# MotorDrive1.net
KiCad netlist of a schematic drawn in Altium Designer
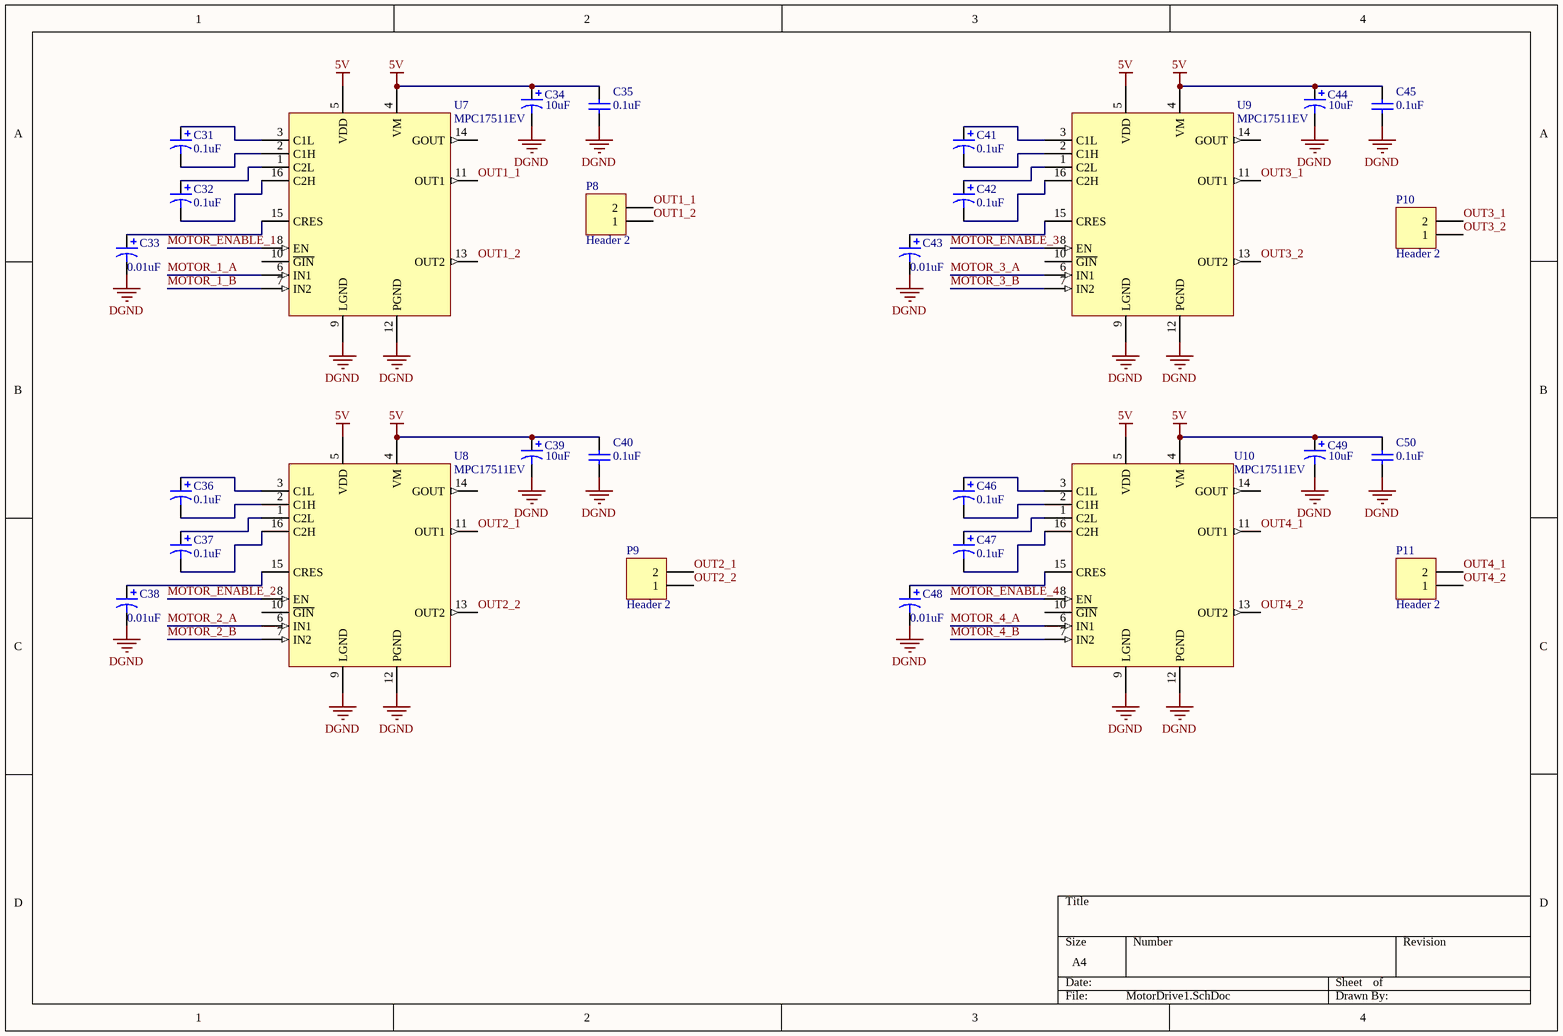
[diagram p0: MotorDrive1.SchDoc]

(export (version "E")
  (design (tool "Eeschema 10.0.6"))
  (components
    (comp (ref "C31")
      (value "0.1uF")
      (footprint "0402")
      (description "Polarized Capacitor (Radial)")
      (fields (field (name "PUBLISHER") "Altium Limited"))
      (libsource (lib "Miscellaneous Devices") (part "Cap Pol1"))
    )
    (comp (ref "C32")
      (value "0.1uF")
      (footprint "0402")
      (description "Polarized Capacitor (Radial)")
      (fields (field (name "PUBLISHER") "Altium Limited"))
      (libsource (lib "Miscellaneous Devices") (part "Cap Pol1"))
    )
    (comp (ref "C33")
      (value "0.01uF")
      (footprint "1608[0603]")
      (description "Polarized Capacitor (Radial)")
      (fields (field (name "PUBLISHER") "Altium Limited"))
      (libsource (lib "Miscellaneous Devices") (part "Cap Pol1"))
    )
    (comp (ref "C34")
      (value "10uF")
      (footprint "1608[0603]")
      (description "Polarized Capacitor (Radial)")
      (fields (field (name "PUBLISHER") "Altium Limited"))
      (libsource (lib "Miscellaneous Devices") (part "Cap Pol1"))
    )
    (comp (ref "C35")
      (value "0.1uF")
      (footprint "1608[0603]")
      (description "Capacitor")
      (fields (field (name "PUBLISHER") "Altium Limited"))
      (libsource (lib "Miscellaneous Devices") (part "Cap"))
    )
    (comp (ref "C36")
      (value "0.1uF")
      (footprint "0402")
      (description "Polarized Capacitor (Radial)")
      (fields (field (name "PUBLISHER") "Altium Limited"))
      (libsource (lib "Miscellaneous Devices") (part "Cap Pol1"))
    )
    (comp (ref "C37")
      (value "0.1uF")
      (footprint "0402")
      (description "Polarized Capacitor (Radial)")
      (fields (field (name "PUBLISHER") "Altium Limited"))
      (libsource (lib "Miscellaneous Devices") (part "Cap Pol1"))
    )
    (comp (ref "C38")
      (value "0.01uF")
      (footprint "1608[0603]")
      (description "Polarized Capacitor (Radial)")
      (fields (field (name "PUBLISHER") "Altium Limited"))
      (libsource (lib "Miscellaneous Devices") (part "Cap Pol1"))
    )
    (comp (ref "C39")
      (value "10uF")
      (footprint "1608[0603]")
      (description "Polarized Capacitor (Radial)")
      (fields (field (name "PUBLISHER") "Altium Limited"))
      (libsource (lib "Miscellaneous Devices") (part "Cap Pol1"))
    )
    (comp (ref "C40")
      (value "0.1uF")
      (footprint "1608[0603]")
      (description "Capacitor")
      (fields (field (name "PUBLISHER") "Altium Limited"))
      (libsource (lib "Miscellaneous Devices") (part "Cap"))
    )
    (comp (ref "C41")
      (value "0.1uF")
      (footprint "0402")
      (description "Polarized Capacitor (Radial)")
      (fields (field (name "PUBLISHER") "Altium Limited"))
      (libsource (lib "Miscellaneous Devices") (part "Cap Pol1"))
    )
    (comp (ref "C42")
      (value "0.1uF")
      (footprint "0402")
      (description "Polarized Capacitor (Radial)")
      (fields (field (name "PUBLISHER") "Altium Limited"))
      (libsource (lib "Miscellaneous Devices") (part "Cap Pol1"))
    )
    (comp (ref "C43")
      (value "0.01uF")
      (footprint "1608[0603]")
      (description "Polarized Capacitor (Radial)")
      (fields (field (name "PUBLISHER") "Altium Limited"))
      (libsource (lib "Miscellaneous Devices") (part "Cap Pol1"))
    )
    (comp (ref "C44")
      (value "10uF")
      (footprint "1608[0603]")
      (description "Polarized Capacitor (Radial)")
      (fields (field (name "PUBLISHER") "Altium Limited"))
      (libsource (lib "Miscellaneous Devices") (part "Cap Pol1"))
    )
    (comp (ref "C45")
      (value "0.1uF")
      (footprint "1608[0603]")
      (description "Capacitor")
      (fields (field (name "PUBLISHER") "Altium Limited"))
      (libsource (lib "Miscellaneous Devices") (part "Cap"))
    )
    (comp (ref "C46")
      (value "0.1uF")
      (footprint "0402")
      (description "Polarized Capacitor (Radial)")
      (fields (field (name "PUBLISHER") "Altium Limited"))
      (libsource (lib "Miscellaneous Devices") (part "Cap Pol1"))
    )
    (comp (ref "C47")
      (value "0.1uF")
      (footprint "0402")
      (description "Polarized Capacitor (Radial)")
      (fields (field (name "PUBLISHER") "Altium Limited"))
      (libsource (lib "Miscellaneous Devices") (part "Cap Pol1"))
    )
    (comp (ref "C48")
      (value "0.01uF")
      (footprint "1608[0603]")
      (description "Polarized Capacitor (Radial)")
      (fields (field (name "PUBLISHER") "Altium Limited"))
      (libsource (lib "Miscellaneous Devices") (part "Cap Pol1"))
    )
    (comp (ref "C49")
      (value "10uF")
      (footprint "1608[0603]")
      (description "Polarized Capacitor (Radial)")
      (fields (field (name "PUBLISHER") "Altium Limited"))
      (libsource (lib "Miscellaneous Devices") (part "Cap Pol1"))
    )
    (comp (ref "C50")
      (value "0.1uF")
      (footprint "1608[0603]")
      (description "Capacitor")
      (fields (field (name "PUBLISHER") "Altium Limited"))
      (libsource (lib "Miscellaneous Devices") (part "Cap"))
    )
    (comp (ref "P8")
      (value "Header 2")
      (footprint "HDR1X2")
      (description "Header, 2-Pin")
      (fields (field (name "PUBLISHER") "Altium Limited"))
      (libsource (lib "Miscellaneous Connectors") (part "Header 2"))
    )
    (comp (ref "P9")
      (value "Header 2")
      (footprint "HDR1X2")
      (description "Header, 2-Pin")
      (fields (field (name "PUBLISHER") "Altium Limited"))
      (libsource (lib "Miscellaneous Connectors") (part "Header 2"))
    )
    (comp (ref "P10")
      (value "Header 2")
      (footprint "HDR1X2")
      (description "Header, 2-Pin")
      (fields (field (name "PUBLISHER") "Altium Limited"))
      (libsource (lib "Miscellaneous Connectors") (part "Header 2"))
    )
    (comp (ref "P11")
      (value "Header 2")
      (footprint "HDR1X2")
      (description "Header, 2-Pin")
      (fields (field (name "PUBLISHER") "Altium Limited"))
      (libsource (lib "Miscellaneous Connectors") (part "Header 2"))
    )
    (comp (ref "U7")
      (value "MPC17511EV")
      (footprint "MPC_motor_drive")
      (description "IC MOTOR DRIVER PAR 16VMFP")
      (libsource (lib "MPC_motor_driver") (part "MPC17511EV"))
    )
    (comp (ref "U8")
      (value "MPC17511EV")
      (footprint "MPC_motor_drive")
      (description "IC MOTOR DRIVER PAR 16VMFP")
      (libsource (lib "MPC_motor_driver") (part "MPC17511EV"))
    )
    (comp (ref "U9")
      (value "MPC17511EV")
      (footprint "MPC_motor_drive")
      (description "IC MOTOR DRIVER PAR 16VMFP")
      (libsource (lib "MPC_motor_driver") (part "MPC17511EV"))
    )
    (comp (ref "U10")
      (value "MPC17511EV")
      (footprint "MPC_motor_drive")
      (description "IC MOTOR DRIVER PAR 16VMFP")
      (libsource (lib "MPC_motor_driver") (part "MPC17511EV"))
    )
  )
  (nets
    (net (code "1") (name "/MOTOR_1_A") (class "Default")
      (node (ref "U7") (pin "6") (pinfunction "IN1_6") (pintype "input"))
    )
    (net (code "2") (name "/MOTOR_1_B") (class "Default")
      (node (ref "U7") (pin "7") (pinfunction "IN2_7") (pintype "input"))
    )
    (net (code "3") (name "/MOTOR_2_A") (class "Default")
      (node (ref "U8") (pin "6") (pinfunction "IN1_6") (pintype "input"))
    )
    (net (code "4") (name "/MOTOR_2_B") (class "Default")
      (node (ref "U8") (pin "7") (pinfunction "IN2_7") (pintype "input"))
    )
    (net (code "5") (name "/MOTOR_3_A") (class "Default")
      (node (ref "U9") (pin "6") (pinfunction "IN1_6") (pintype "input"))
    )
    (net (code "6") (name "/MOTOR_3_B") (class "Default")
      (node (ref "U9") (pin "7") (pinfunction "IN2_7") (pintype "input"))
    )
    (net (code "7") (name "/MOTOR_4_A") (class "Default")
      (node (ref "U10") (pin "6") (pinfunction "IN1_6") (pintype "input"))
    )
    (net (code "8") (name "/MOTOR_4_B") (class "Default")
      (node (ref "U10") (pin "7") (pinfunction "IN2_7") (pintype "input"))
    )
    (net (code "9") (name "/MOTOR_ENABLE_1") (class "Default")
      (node (ref "U7") (pin "8") (pinfunction "EN_8") (pintype "input"))
    )
    (net (code "10") (name "/MOTOR_ENABLE_2") (class "Default")
      (node (ref "U8") (pin "8") (pinfunction "EN_8") (pintype "input"))
    )
    (net (code "11") (name "/MOTOR_ENABLE_3") (class "Default")
      (node (ref "U9") (pin "8") (pinfunction "EN_8") (pintype "input"))
    )
    (net (code "12") (name "/MOTOR_ENABLE_4") (class "Default")
      (node (ref "U10") (pin "8") (pinfunction "EN_8") (pintype "input"))
    )
    (net (code "13") (name "/OUT1_1") (class "Default")
      (node (ref "P8") (pin "2") (pinfunction "2_2") (pintype "passive"))
      (node (ref "U7") (pin "11") (pinfunction "OUT1_11") (pintype "output"))
    )
    (net (code "14") (name "/OUT1_2") (class "Default")
      (node (ref "P8") (pin "1") (pinfunction "1_1") (pintype "passive"))
      (node (ref "U7") (pin "13") (pinfunction "OUT2_13") (pintype "output"))
    )
    (net (code "15") (name "/OUT2_1") (class "Default")
      (node (ref "P9") (pin "2") (pinfunction "2_2") (pintype "passive"))
      (node (ref "U8") (pin "11") (pinfunction "OUT1_11") (pintype "output"))
    )
    (net (code "16") (name "/OUT2_2") (class "Default")
      (node (ref "P9") (pin "1") (pinfunction "1_1") (pintype "passive"))
      (node (ref "U8") (pin "13") (pinfunction "OUT2_13") (pintype "output"))
    )
    (net (code "17") (name "/OUT3_1") (class "Default")
      (node (ref "P10") (pin "2") (pinfunction "2_2") (pintype "passive"))
      (node (ref "U9") (pin "11") (pinfunction "OUT1_11") (pintype "output"))
    )
    (net (code "18") (name "/OUT3_2") (class "Default")
      (node (ref "P10") (pin "1") (pinfunction "1_1") (pintype "passive"))
      (node (ref "U9") (pin "13") (pinfunction "OUT2_13") (pintype "output"))
    )
    (net (code "19") (name "/OUT4_1") (class "Default")
      (node (ref "P11") (pin "2") (pinfunction "2_2") (pintype "passive"))
      (node (ref "U10") (pin "11") (pinfunction "OUT1_11") (pintype "output"))
    )
    (net (code "20") (name "/OUT4_2") (class "Default")
      (node (ref "P11") (pin "1") (pinfunction "1_1") (pintype "passive"))
      (node (ref "U10") (pin "13") (pinfunction "OUT2_13") (pintype "output"))
    )
    (net (code "21") (name "5V") (class "Default")
      (node (ref "C34") (pin "1") (pinfunction "1_1") (pintype "passive"))
      (node (ref "C35") (pin "2") (pinfunction "2_2") (pintype "passive"))
      (node (ref "C39") (pin "1") (pinfunction "1_1") (pintype "passive"))
      (node (ref "C40") (pin "2") (pinfunction "2_2") (pintype "passive"))
      (node (ref "C44") (pin "1") (pinfunction "1_1") (pintype "passive"))
      (node (ref "C45") (pin "2") (pinfunction "2_2") (pintype "passive"))
      (node (ref "C49") (pin "1") (pinfunction "1_1") (pintype "passive"))
      (node (ref "C50") (pin "2") (pinfunction "2_2") (pintype "passive"))
      (node (ref "U10") (pin "4") (pinfunction "VM_4") (pintype "power_in"))
      (node (ref "U10") (pin "5") (pinfunction "VDD_5") (pintype "power_in"))
      (node (ref "U7") (pin "4") (pinfunction "VM_4") (pintype "power_in"))
      (node (ref "U7") (pin "5") (pinfunction "VDD_5") (pintype "power_in"))
      (node (ref "U8") (pin "4") (pinfunction "VM_4") (pintype "power_in"))
      (node (ref "U8") (pin "5") (pinfunction "VDD_5") (pintype "power_in"))
      (node (ref "U9") (pin "4") (pinfunction "VM_4") (pintype "power_in"))
      (node (ref "U9") (pin "5") (pinfunction "VDD_5") (pintype "power_in"))
    )
    (net (code "22") (name "DGND") (class "Default")
      (node (ref "C33") (pin "2") (pinfunction "2_2") (pintype "passive"))
      (node (ref "C34") (pin "2") (pinfunction "2_2") (pintype "passive"))
      (node (ref "C35") (pin "1") (pinfunction "1_1") (pintype "passive"))
      (node (ref "C38") (pin "2") (pinfunction "2_2") (pintype "passive"))
      (node (ref "C39") (pin "2") (pinfunction "2_2") (pintype "passive"))
      (node (ref "C40") (pin "1") (pinfunction "1_1") (pintype "passive"))
      (node (ref "C43") (pin "2") (pinfunction "2_2") (pintype "passive"))
      (node (ref "C44") (pin "2") (pinfunction "2_2") (pintype "passive"))
      (node (ref "C45") (pin "1") (pinfunction "1_1") (pintype "passive"))
      (node (ref "C48") (pin "2") (pinfunction "2_2") (pintype "passive"))
      (node (ref "C49") (pin "2") (pinfunction "2_2") (pintype "passive"))
      (node (ref "C50") (pin "1") (pinfunction "1_1") (pintype "passive"))
      (node (ref "U10") (pin "12") (pinfunction "PGND_12") (pintype "passive"))
      (node (ref "U10") (pin "9") (pinfunction "LGND_9") (pintype "passive"))
      (node (ref "U7") (pin "12") (pinfunction "PGND_12") (pintype "passive"))
      (node (ref "U7") (pin "9") (pinfunction "LGND_9") (pintype "passive"))
      (node (ref "U8") (pin "12") (pinfunction "PGND_12") (pintype "passive"))
      (node (ref "U8") (pin "9") (pinfunction "LGND_9") (pintype "passive"))
      (node (ref "U9") (pin "12") (pinfunction "PGND_12") (pintype "passive"))
      (node (ref "U9") (pin "9") (pinfunction "LGND_9") (pintype "passive"))
    )
    (net (code "23") (name "Net-(U7-C1H)") (class "Default")
      (node (ref "C31") (pin "2") (pinfunction "2_2") (pintype "passive"))
      (node (ref "U7") (pin "2") (pinfunction "C1H_2") (pintype "passive"))
    )
    (net (code "24") (name "Net-(U7-C1L)") (class "Default")
      (node (ref "C31") (pin "1") (pinfunction "1_1") (pintype "passive"))
      (node (ref "U7") (pin "3") (pinfunction "C1L_3") (pintype "passive"))
    )
    (net (code "25") (name "Net-(U7-C2H)") (class "Default")
      (node (ref "C32") (pin "2") (pinfunction "2_2") (pintype "passive"))
      (node (ref "U7") (pin "16") (pinfunction "C2H_16") (pintype "passive"))
    )
    (net (code "26") (name "Net-(U7-C2L)") (class "Default")
      (node (ref "C32") (pin "1") (pinfunction "1_1") (pintype "passive"))
      (node (ref "U7") (pin "1") (pinfunction "C2L_1") (pintype "passive"))
    )
    (net (code "27") (name "Net-(U7-CRES)") (class "Default")
      (node (ref "C33") (pin "1") (pinfunction "1_1") (pintype "passive"))
      (node (ref "U7") (pin "15") (pinfunction "CRES_15") (pintype "passive"))
    )
    (net (code "28") (name "Net-(U8-C1H)") (class "Default")
      (node (ref "C36") (pin "2") (pinfunction "2_2") (pintype "passive"))
      (node (ref "U8") (pin "2") (pinfunction "C1H_2") (pintype "passive"))
    )
    (net (code "29") (name "Net-(U8-C1L)") (class "Default")
      (node (ref "C36") (pin "1") (pinfunction "1_1") (pintype "passive"))
      (node (ref "U8") (pin "3") (pinfunction "C1L_3") (pintype "passive"))
    )
    (net (code "30") (name "Net-(U8-C2H)") (class "Default")
      (node (ref "C37") (pin "2") (pinfunction "2_2") (pintype "passive"))
      (node (ref "U8") (pin "16") (pinfunction "C2H_16") (pintype "passive"))
    )
    (net (code "31") (name "Net-(U8-C2L)") (class "Default")
      (node (ref "C37") (pin "1") (pinfunction "1_1") (pintype "passive"))
      (node (ref "U8") (pin "1") (pinfunction "C2L_1") (pintype "passive"))
    )
    (net (code "32") (name "Net-(U8-CRES)") (class "Default")
      (node (ref "C38") (pin "1") (pinfunction "1_1") (pintype "passive"))
      (node (ref "U8") (pin "15") (pinfunction "CRES_15") (pintype "passive"))
    )
    (net (code "33") (name "Net-(U9-C1H)") (class "Default")
      (node (ref "C41") (pin "2") (pinfunction "2_2") (pintype "passive"))
      (node (ref "U9") (pin "2") (pinfunction "C1H_2") (pintype "passive"))
    )
    (net (code "34") (name "Net-(U9-C1L)") (class "Default")
      (node (ref "C41") (pin "1") (pinfunction "1_1") (pintype "passive"))
      (node (ref "U9") (pin "3") (pinfunction "C1L_3") (pintype "passive"))
    )
    (net (code "35") (name "Net-(U9-C2H)") (class "Default")
      (node (ref "C42") (pin "2") (pinfunction "2_2") (pintype "passive"))
      (node (ref "U9") (pin "16") (pinfunction "C2H_16") (pintype "passive"))
    )
    (net (code "36") (name "Net-(U9-C2L)") (class "Default")
      (node (ref "C42") (pin "1") (pinfunction "1_1") (pintype "passive"))
      (node (ref "U9") (pin "1") (pinfunction "C2L_1") (pintype "passive"))
    )
    (net (code "37") (name "Net-(U9-CRES)") (class "Default")
      (node (ref "C43") (pin "1") (pinfunction "1_1") (pintype "passive"))
      (node (ref "U9") (pin "15") (pinfunction "CRES_15") (pintype "passive"))
    )
    (net (code "38") (name "Net-(U10-C1H)") (class "Default")
      (node (ref "C46") (pin "2") (pinfunction "2_2") (pintype "passive"))
      (node (ref "U10") (pin "2") (pinfunction "C1H_2") (pintype "passive"))
    )
    (net (code "39") (name "Net-(U10-C1L)") (class "Default")
      (node (ref "C46") (pin "1") (pinfunction "1_1") (pintype "passive"))
      (node (ref "U10") (pin "3") (pinfunction "C1L_3") (pintype "passive"))
    )
    (net (code "40") (name "Net-(U10-C2H)") (class "Default")
      (node (ref "C47") (pin "2") (pinfunction "2_2") (pintype "passive"))
      (node (ref "U10") (pin "16") (pinfunction "C2H_16") (pintype "passive"))
    )
    (net (code "41") (name "Net-(U10-C2L)") (class "Default")
      (node (ref "C47") (pin "1") (pinfunction "1_1") (pintype "passive"))
      (node (ref "U10") (pin "1") (pinfunction "C2L_1") (pintype "passive"))
    )
    (net (code "42") (name "Net-(U10-CRES)") (class "Default")
      (node (ref "C48") (pin "1") (pinfunction "1_1") (pintype "passive"))
      (node (ref "U10") (pin "15") (pinfunction "CRES_15") (pintype "passive"))
    )
    (net (code "43") (name "unconnected-(U7-GOUT-Pad14)") (class "Default")
      (node (ref "U7") (pin "14") (pinfunction "GOUT_14") (pintype "output"))
    )
    (net (code "44") (name "unconnected-(U7-~{GIN}-Pad10)") (class "Default")
      (node (ref "U7") (pin "10") (pinfunction "~{GIN}_10") (pintype "passive"))
    )
    (net (code "45") (name "unconnected-(U8-GOUT-Pad14)") (class "Default")
      (node (ref "U8") (pin "14") (pinfunction "GOUT_14") (pintype "output"))
    )
    (net (code "46") (name "unconnected-(U8-~{GIN}-Pad10)") (class "Default")
      (node (ref "U8") (pin "10") (pinfunction "~{GIN}_10") (pintype "passive"))
    )
    (net (code "47") (name "unconnected-(U9-GOUT-Pad14)") (class "Default")
      (node (ref "U9") (pin "14") (pinfunction "GOUT_14") (pintype "output"))
    )
    (net (code "48") (name "unconnected-(U9-~{GIN}-Pad10)") (class "Default")
      (node (ref "U9") (pin "10") (pinfunction "~{GIN}_10") (pintype "passive"))
    )
    (net (code "49") (name "unconnected-(U10-GOUT-Pad14)") (class "Default")
      (node (ref "U10") (pin "14") (pinfunction "GOUT_14") (pintype "output"))
    )
    (net (code "50") (name "unconnected-(U10-~{GIN}-Pad10)") (class "Default")
      (node (ref "U10") (pin "10") (pinfunction "~{GIN}_10") (pintype "passive"))
    )
  )
)
